# FEV-60_Motor_Driver_Mcu.net
KiCad netlist of a schematic drawn in Altium Designer
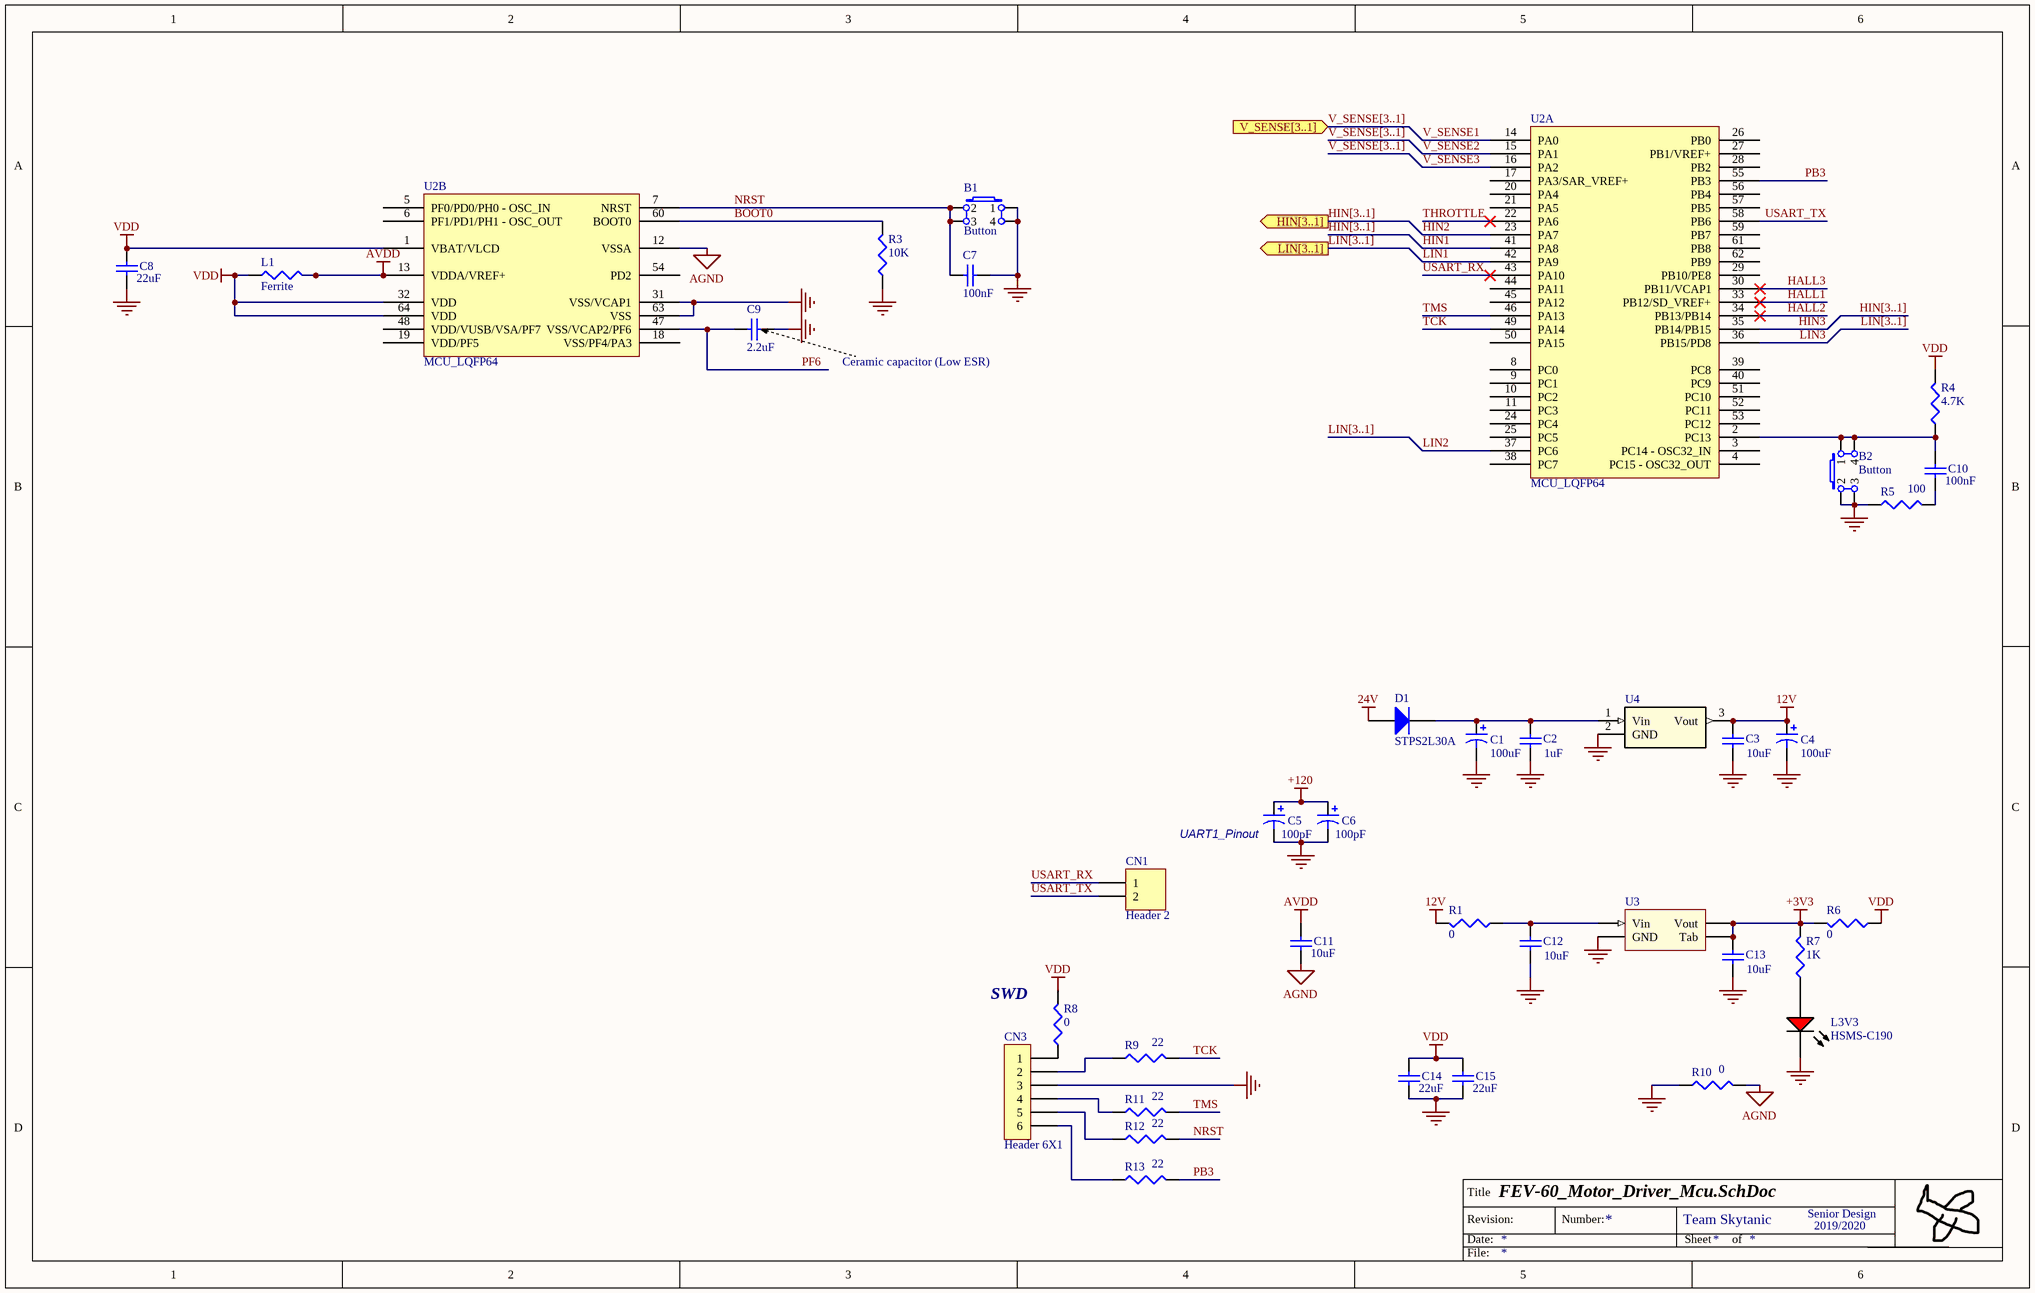
[diagram p0: FEV-60_Motor_Driver_Mcu.SchDoc]

(export (version "E")
  (design (tool "Eeschema 10.0.6"))
  (components
    (comp (ref "B1")
      (value "Button")
      (footprint "Button - duplicate")
      (libsource (lib "FEV-60_Lib") (part "Button"))
    )
    (comp (ref "B2")
      (value "Button")
      (footprint "Button - duplicate")
      (libsource (lib "FEV-60_Lib") (part "Button"))
    )
    (comp (ref "C1")
      (value "100uF")
      (footprint "UVY1V101MED1TD")
      (description "Polarized Capacitor (Axial)")
      (fields (field (name "Comment") "UVY1V101MED1TD") (field (name "PUBLISHER") "Altium Limited"))
      (libsource (lib "FEV-60_Lib") (part "UVY1V101MED1TD"))
    )
    (comp (ref "C2")
      (value "1uF")
      (footprint "1608[0603]")
      (description "Capacitor (Semiconductor SIM Model)")
      (fields (field (name "Comment") "Cap Semi") (field (name "PUBLISHER") "Altium Limited"))
      (libsource (lib "Miscellaneous Devices") (part "Cap Semi"))
    )
    (comp (ref "C3")
      (value "10uF")
      (footprint "1608[0603]")
      (description "Capacitor (Semiconductor SIM Model)")
      (fields (field (name "Comment") "Cap Semi") (field (name "PUBLISHER") "Altium Limited"))
      (libsource (lib "Miscellaneous Devices") (part "Cap Semi"))
    )
    (comp (ref "C4")
      (value "100uF")
      (footprint "UVY1V101MED1TD")
      (description "Polarized Capacitor (Axial)")
      (fields (field (name "Comment") "UVY1V101MED1TD") (field (name "PUBLISHER") "Altium Limited"))
      (libsource (lib "FEV-60_Lib") (part "UVY1V101MED1TD"))
    )
    (comp (ref "C5")
      (value "100pF")
      (footprint "UCS2D151MHD1TN")
      (description "Polarized Capacitor (Axial)")
      (fields (field (name "Comment") "UCS2D151MHD1TN") (field (name "PUBLISHER") "Altium Limited"))
      (libsource (lib "FEV-60_Lib") (part "UCS2D151MHD1TN"))
    )
    (comp (ref "C6")
      (value "100pF")
      (footprint "UCS2D151MHD1TN")
      (description "Polarized Capacitor (Axial)")
      (fields (field (name "Comment") "UCS2D151MHD1TN") (field (name "PUBLISHER") "Altium Limited"))
      (libsource (lib "FEV-60_Lib") (part "UCS2D151MHD1TN"))
    )
    (comp (ref "C7")
      (value "100nF")
      (footprint "1608[0603]")
      (description "Capacitor (Semiconductor SIM Model)")
      (fields (field (name "Comment") "Cap Semi") (field (name "PUBLISHER") "Altium Limited"))
      (libsource (lib "Miscellaneous Devices") (part "Cap Semi"))
    )
    (comp (ref "C8")
      (value "22uF")
      (footprint "1608[0603]")
      (description "Capacitor (Semiconductor SIM Model)")
      (fields (field (name "Comment") "Cap Semi") (field (name "PUBLISHER") "Altium Limited"))
      (libsource (lib "Miscellaneous Devices") (part "Cap Semi"))
    )
    (comp (ref "C9")
      (value "2.2uF")
      (footprint "1608[0603]")
      (description "Capacitor (Semiconductor SIM Model)")
      (fields (field (name "Comment") "Cap Semi") (field (name "PUBLISHER") "Altium Limited"))
      (libsource (lib "Miscellaneous Devices") (part "Cap Semi"))
    )
    (comp (ref "C10")
      (value "100nF")
      (footprint "1608[0603]")
      (description "Capacitor (Semiconductor SIM Model)")
      (fields (field (name "Comment") "Cap Semi") (field (name "PUBLISHER") "Altium Limited"))
      (libsource (lib "Miscellaneous Devices") (part "Cap Semi"))
    )
    (comp (ref "C11")
      (value "10uF")
      (footprint "1608[0603]")
      (description "Capacitor (Semiconductor SIM Model)")
      (fields (field (name "Comment") "Cap Semi") (field (name "PUBLISHER") "Altium Limited"))
      (libsource (lib "Miscellaneous Devices") (part "Cap Semi"))
    )
    (comp (ref "C12")
      (value "10uF")
      (footprint "1608[0603]")
      (description "Capacitor (Semiconductor SIM Model)")
      (fields (field (name "Comment") "Cap Semi") (field (name "PUBLISHER") "Altium Limited"))
      (libsource (lib "Miscellaneous Devices") (part "Cap Semi"))
    )
    (comp (ref "C13")
      (value "10uF")
      (footprint "1608[0603]")
      (description "Capacitor (Semiconductor SIM Model)")
      (fields (field (name "Comment") "Cap Semi") (field (name "PUBLISHER") "Altium Limited"))
      (libsource (lib "Miscellaneous Devices") (part "Cap Semi"))
    )
    (comp (ref "C14")
      (value "22uF")
      (footprint "1608[0603]")
      (description "Capacitor (Semiconductor SIM Model)")
      (fields (field (name "Comment") "Cap Semi") (field (name "PUBLISHER") "Altium Limited"))
      (libsource (lib "Miscellaneous Devices") (part "Cap Semi"))
    )
    (comp (ref "C15")
      (value "22uF")
      (footprint "1608[0603]")
      (description "Capacitor (Semiconductor SIM Model)")
      (fields (field (name "Comment") "Cap Semi") (field (name "PUBLISHER") "Altium Limited"))
      (libsource (lib "Miscellaneous Devices") (part "Cap Semi"))
    )
    (comp (ref "CN1")
      (value "Header 2")
      (footprint "HDR1X2")
      (description "Header, 2-Pin")
      (fields (field (name "PUBLISHER") "Altium Limited"))
      (libsource (lib "Miscellaneous Connectors") (part "Header 2"))
    )
    (comp (ref "CN3")
      (value "Header 6X1")
      (footprint "HDR1X6")
      (description "Header, 6-Pin, Single row")
      (fields (field (name "PUBLISHER") "Altium Limited"))
      (libsource (lib "Nucleo_64") (part "Header 6X1"))
    )
    (comp (ref "D1")
      (value "STPS2L30A")
      (footprint "STPS2L30A")
      (libsource (lib "FEV-60_Lib") (part "STPS2L30A"))
    )
    (comp (ref "L1")
      (value "Ferrite")
      (footprint "J1-0603")
      (description "Resistor")
      (fields (field (name "PUBLISHER") "Altium Limited"))
      (libsource (lib "Miscellaneous Devices") (part "Res3"))
    )
    (comp (ref "L3V3")
      (value "HSMS-C190")
      (footprint "AVAG-HSMX-C190_V")
      (description "LED Uni-Color Red, 52 mW, 20 mA, -40 to 85 degC, 2-Pin SMD, RoHS, Tape and Reel")
      (fields (field (name "MANUFACTURER") "Avago"))
      (libsource (lib "Altium Content Vault") (part "LED-RED-AK-2"))
    )
    (comp (ref "R1")
      (value "0")
      (footprint "J1-0603")
      (description "Resistor")
      (fields (field (name "Comment") "Res3") (field (name "PUBLISHER") "Altium Limited"))
      (libsource (lib "Miscellaneous Devices") (part "Res3"))
    )
    (comp (ref "R3")
      (value "10K")
      (footprint "J1-0603")
      (description "Resistor")
      (fields (field (name "Comment") "Res3") (field (name "PUBLISHER") "Altium Limited"))
      (libsource (lib "Miscellaneous Devices") (part "Res3"))
    )
    (comp (ref "R4")
      (value "4.7K")
      (footprint "J1-0603")
      (description "Resistor")
      (fields (field (name "Comment") "Res3") (field (name "PUBLISHER") "Altium Limited"))
      (libsource (lib "Miscellaneous Devices") (part "Res3"))
    )
    (comp (ref "R5")
      (value "100")
      (footprint "J1-0603")
      (description "Resistor")
      (fields (field (name "Comment") "Res3") (field (name "PUBLISHER") "Altium Limited"))
      (libsource (lib "Miscellaneous Devices") (part "Res3"))
    )
    (comp (ref "R6")
      (value "0")
      (footprint "J1-0603")
      (description "Resistor")
      (fields (field (name "Comment") "Res3") (field (name "PUBLISHER") "Altium Limited"))
      (libsource (lib "Miscellaneous Devices") (part "Res3"))
    )
    (comp (ref "R7")
      (value "1K")
      (footprint "J1-0603")
      (description "Resistor")
      (fields (field (name "Comment") "Res3") (field (name "PUBLISHER") "Altium Limited"))
      (libsource (lib "Miscellaneous Devices") (part "Res3"))
    )
    (comp (ref "R8")
      (value "0")
      (footprint "J1-0603")
      (description "Resistor")
      (fields (field (name "Comment") "Res3") (field (name "PUBLISHER") "Altium Limited"))
      (libsource (lib "Miscellaneous Devices") (part "Res3"))
    )
    (comp (ref "R9")
      (value "22")
      (footprint "J1-0603")
      (description "Resistor")
      (fields (field (name "Comment") "Res3") (field (name "PUBLISHER") "Altium Limited"))
      (libsource (lib "Miscellaneous Devices") (part "Res3"))
    )
    (comp (ref "R10")
      (value "0")
      (footprint "J1-0603")
      (description "Resistor")
      (fields (field (name "Comment") "Res3") (field (name "PUBLISHER") "Altium Limited"))
      (libsource (lib "Miscellaneous Devices") (part "Res3"))
    )
    (comp (ref "R11")
      (value "22")
      (footprint "J1-0603")
      (description "Resistor")
      (fields (field (name "Comment") "Res3") (field (name "PUBLISHER") "Altium Limited"))
      (libsource (lib "Miscellaneous Devices") (part "Res3"))
    )
    (comp (ref "R12")
      (value "22")
      (footprint "J1-0603")
      (description "Resistor")
      (fields (field (name "Comment") "Res3") (field (name "PUBLISHER") "Altium Limited"))
      (libsource (lib "Miscellaneous Devices") (part "Res3"))
    )
    (comp (ref "R13")
      (value "22")
      (footprint "J1-0603")
      (description "Resistor")
      (fields (field (name "Comment") "Res3") (field (name "PUBLISHER") "Altium Limited"))
      (libsource (lib "Miscellaneous Devices") (part "Res3"))
    )
    (comp (ref "U2")
      (value "MCU_LQFP64")
      (footprint "STM32F030R8 - duplicate")
      (libsource (lib "FEV-60_Lib") (part "MCU_LQFP64"))
    )
    (comp (ref "U3")
      (value "LD1117S33TR")
      (footprint "LD1117S33TR - duplicate")
      (libsource (lib "FEV-60_Lib") (part "LD1117S33TR"))
    )
    (comp (ref "U4")
      (value "UA78M12CKVURG3")
      (footprint "UA78M12CKVURG3")
      (description "No Description Available")
      (fields
        (field (name "MANUFACTURER") "Texas Instruments")
        (field (name "COPYRIGHT") "Copyright (C) 2018 Accelerated Designs. All rights reserved")
      )
      (libsource (lib "FEV-60_Lib") (part "UA78M12CKVURG3"))
    )
  )
  (nets
    (net (code "1") (name "+3V3") (class "Default")
      (node (ref "C13") (pin "2") (pinfunction "2_2") (pintype "passive"))
      (node (ref "R6") (pin "2") (pinfunction "2_2") (pintype "passive"))
      (node (ref "R7") (pin "2") (pinfunction "2_2") (pintype "passive"))
      (node (ref "U3") (pin "2") (pinfunction "Vout_2") (pintype "passive"))
      (node (ref "U3") (pin "4") (pinfunction "Tab_4") (pintype "passive"))
    )
    (net (code "2") (name "+120") (class "Default")
      (node (ref "C5") (pin "1") (pinfunction "1_1") (pintype "passive"))
      (node (ref "C6") (pin "1") (pinfunction "1_1") (pintype "passive"))
    )
    (net (code "3") (name "/BOOT0") (class "Default")
      (node (ref "R3") (pin "2") (pinfunction "2_2") (pintype "passive"))
      (node (ref "U2") (pin "60") (pinfunction "BOOT0_60") (pintype "passive"))
    )
    (net (code "4") (name "/HALL1") (class "Default")
      (node (ref "U2") (pin "33") (pinfunction "PB12/SD_VREF+_33") (pintype "passive+no_connect"))
    )
    (net (code "5") (name "/HALL2") (class "Default")
      (node (ref "U2") (pin "34") (pinfunction "PB13/PB14_34") (pintype "passive+no_connect"))
    )
    (net (code "6") (name "/HALL3") (class "Default")
      (node (ref "U2") (pin "30") (pinfunction "PB11/VCAP1_30") (pintype "passive+no_connect"))
    )
    (net (code "7") (name "/HIN1") (class "Default")
      (node (ref "U2") (pin "41") (pinfunction "PA8_41") (pintype "passive"))
    )
    (net (code "8") (name "/HIN2") (class "Default")
      (node (ref "U2") (pin "23") (pinfunction "PA7_23") (pintype "passive"))
    )
    (net (code "9") (name "/HIN3") (class "Default")
      (node (ref "U2") (pin "35") (pinfunction "PB14/PB15_35") (pintype "passive"))
    )
    (net (code "11") (name "/LIN1") (class "Default")
      (node (ref "U2") (pin "42") (pinfunction "PA9_42") (pintype "passive"))
    )
    (net (code "12") (name "/LIN2") (class "Default")
      (node (ref "U2") (pin "37") (pinfunction "PC6_37") (pintype "passive"))
    )
    (net (code "13") (name "/LIN3") (class "Default")
      (node (ref "U2") (pin "36") (pinfunction "PB15/PD8_36") (pintype "passive"))
    )
    (net (code "15") (name "/NRST") (class "Default")
      (node (ref "B1") (pin "2") (pinfunction "2_2") (pintype "passive"))
      (node (ref "B1") (pin "3") (pinfunction "3_3") (pintype "passive"))
      (node (ref "C7") (pin "2") (pinfunction "2_2") (pintype "passive"))
      (node (ref "R12") (pin "2") (pinfunction "2_2") (pintype "passive"))
      (node (ref "U2") (pin "7") (pinfunction "NRST_7") (pintype "passive"))
    )
    (net (code "16") (name "/PB3") (class "Default")
      (node (ref "R13") (pin "2") (pinfunction "2_2") (pintype "passive"))
      (node (ref "U2") (pin "55") (pinfunction "PB3_55") (pintype "passive"))
    )
    (net (code "17") (name "/PF6") (class "Default")
      (node (ref "C9") (pin "2") (pinfunction "2_2") (pintype "passive"))
      (node (ref "U2") (pin "47") (pinfunction "VSS/VCAP2/PF6_47") (pintype "passive"))
    )
    (net (code "18") (name "/TCK") (class "Default")
      (node (ref "R9") (pin "2") (pinfunction "2_2") (pintype "passive"))
      (node (ref "U2") (pin "49") (pinfunction "PA14_49") (pintype "passive"))
    )
    (net (code "19") (name "/THROTTLE") (class "Default")
      (node (ref "U2") (pin "22") (pinfunction "PA6_22") (pintype "passive+no_connect"))
    )
    (net (code "20") (name "/TMS") (class "Default")
      (node (ref "R11") (pin "2") (pinfunction "2_2") (pintype "passive"))
      (node (ref "U2") (pin "46") (pinfunction "PA13_46") (pintype "passive"))
    )
    (net (code "21") (name "/USART_RX") (class "Default")
      (node (ref "CN1") (pin "1") (pinfunction "1_1") (pintype "passive"))
      (node (ref "U2") (pin "43") (pinfunction "PA10_43") (pintype "passive"))
    )
    (net (code "22") (name "/USART_TX") (class "Default")
      (node (ref "CN1") (pin "2") (pinfunction "2_2") (pintype "passive"))
      (node (ref "U2") (pin "58") (pinfunction "PB6_58") (pintype "passive"))
    )
    (net (code "23") (name "/V_SENSE1") (class "Default")
      (node (ref "U2") (pin "14") (pinfunction "PA0_14") (pintype "passive"))
    )
    (net (code "24") (name "/V_SENSE2") (class "Default")
      (node (ref "U2") (pin "15") (pinfunction "PA1_15") (pintype "passive"))
    )
    (net (code "25") (name "/V_SENSE3") (class "Default")
      (node (ref "U2") (pin "16") (pinfunction "PA2_16") (pintype "passive"))
    )
    (net (code "27") (name "12V") (class "Default")
      (node (ref "C3") (pin "2") (pinfunction "2_2") (pintype "passive"))
      (node (ref "C4") (pin "1") (pinfunction "1_1") (pintype "passive"))
      (node (ref "R1") (pin "2") (pinfunction "2_2") (pintype "passive"))
      (node (ref "U4") (pin "3") (pinfunction "Vout_3") (pintype "output"))
    )
    (net (code "28") (name "24V") (class "Default")
      (node (ref "D1") (pin "1") (pinfunction "A_1") (pintype "passive"))
    )
    (net (code "29") (name "AGND") (class "Default")
      (node (ref "C11") (pin "1") (pinfunction "1_1") (pintype "passive"))
      (node (ref "R10") (pin "2") (pinfunction "2_2") (pintype "passive"))
      (node (ref "U2") (pin "12") (pinfunction "VSSA_12") (pintype "passive"))
    )
    (net (code "30") (name "AVDD") (class "Default")
      (node (ref "C11") (pin "2") (pinfunction "2_2") (pintype "passive"))
      (node (ref "L1") (pin "2") (pinfunction "2_2") (pintype "passive"))
      (node (ref "U2") (pin "13") (pinfunction "VDDA/VREF+_13") (pintype "passive"))
    )
    (net (code "31") (name "GND") (class "Default")
      (node (ref "B1") (pin "1") (pinfunction "1_1") (pintype "passive"))
      (node (ref "B1") (pin "4") (pinfunction "4_4") (pintype "passive"))
      (node (ref "B2") (pin "2") (pinfunction "2_2") (pintype "passive"))
      (node (ref "B2") (pin "3") (pinfunction "3_3") (pintype "passive"))
      (node (ref "C1") (pin "2") (pinfunction "2_2") (pintype "passive"))
      (node (ref "C12") (pin "1") (pinfunction "1_1") (pintype "passive"))
      (node (ref "C13") (pin "1") (pinfunction "1_1") (pintype "passive"))
      (node (ref "C14") (pin "1") (pinfunction "1_1") (pintype "passive"))
      (node (ref "C15") (pin "1") (pinfunction "1_1") (pintype "passive"))
      (node (ref "C2") (pin "1") (pinfunction "1_1") (pintype "passive"))
      (node (ref "C3") (pin "1") (pinfunction "1_1") (pintype "passive"))
      (node (ref "C4") (pin "2") (pinfunction "2_2") (pintype "passive"))
      (node (ref "C5") (pin "2") (pinfunction "2_2") (pintype "passive"))
      (node (ref "C6") (pin "2") (pinfunction "2_2") (pintype "passive"))
      (node (ref "C7") (pin "1") (pinfunction "1_1") (pintype "passive"))
      (node (ref "C8") (pin "1") (pinfunction "1_1") (pintype "passive"))
      (node (ref "C9") (pin "1") (pinfunction "1_1") (pintype "passive"))
      (node (ref "CN3") (pin "3") (pinfunction "3_3") (pintype "passive"))
      (node (ref "L3V3") (pin "2") (pinfunction "K_2") (pintype "passive"))
      (node (ref "R10") (pin "1") (pinfunction "1_1") (pintype "passive"))
      (node (ref "R3") (pin "1") (pinfunction "1_1") (pintype "passive"))
      (node (ref "R5") (pin "1") (pinfunction "1_1") (pintype "passive"))
      (node (ref "U2") (pin "31") (pinfunction "VSS/VCAP1_31") (pintype "passive"))
      (node (ref "U2") (pin "63") (pinfunction "VSS_63") (pintype "passive"))
      (node (ref "U3") (pin "1") (pinfunction "GND_1") (pintype "passive"))
      (node (ref "U4") (pin "2") (pinfunction "GND_2") (pintype "power_in"))
    )
    (net (code "32") (name "Net-(C10-Pad1)") (class "Default")
      (node (ref "C10") (pin "1") (pinfunction "1_1") (pintype "passive"))
      (node (ref "R5") (pin "2") (pinfunction "2_2") (pintype "passive"))
    )
    (net (code "33") (name "Net-(CN3-Pad1)") (class "Default")
      (node (ref "CN3") (pin "1") (pinfunction "1_1") (pintype "passive"))
      (node (ref "R8") (pin "1") (pinfunction "1_1") (pintype "passive"))
    )
    (net (code "34") (name "Net-(CN3-Pad2)") (class "Default")
      (node (ref "CN3") (pin "2") (pinfunction "2_2") (pintype "passive"))
      (node (ref "R9") (pin "1") (pinfunction "1_1") (pintype "passive"))
    )
    (net (code "35") (name "Net-(CN3-Pad4)") (class "Default")
      (node (ref "CN3") (pin "4") (pinfunction "4_4") (pintype "passive"))
      (node (ref "R11") (pin "1") (pinfunction "1_1") (pintype "passive"))
    )
    (net (code "36") (name "Net-(CN3-Pad5)") (class "Default")
      (node (ref "CN3") (pin "5") (pinfunction "5_5") (pintype "passive"))
      (node (ref "R12") (pin "1") (pinfunction "1_1") (pintype "passive"))
    )
    (net (code "37") (name "Net-(CN3-Pad6)") (class "Default")
      (node (ref "CN3") (pin "6") (pinfunction "6_6") (pintype "passive"))
      (node (ref "R13") (pin "1") (pinfunction "1_1") (pintype "passive"))
    )
    (net (code "38") (name "Net-(D1-K)") (class "Default")
      (node (ref "C1") (pin "1") (pinfunction "1_1") (pintype "passive"))
      (node (ref "C2") (pin "2") (pinfunction "2_2") (pintype "passive"))
      (node (ref "D1") (pin "2") (pinfunction "K_2") (pintype "passive"))
      (node (ref "U4") (pin "1") (pinfunction "Vin_1") (pintype "input"))
    )
    (net (code "39") (name "Net-(L3V3-A)") (class "Default")
      (node (ref "L3V3") (pin "1") (pinfunction "A_1") (pintype "passive"))
      (node (ref "R7") (pin "1") (pinfunction "1_1") (pintype "passive"))
    )
    (net (code "40") (name "Net-(U2A-PC13)") (class "Default")
      (node (ref "B2") (pin "1") (pinfunction "1_1") (pintype "passive"))
      (node (ref "B2") (pin "4") (pinfunction "4_4") (pintype "passive"))
      (node (ref "C10") (pin "2") (pinfunction "2_2") (pintype "passive"))
      (node (ref "R4") (pin "1") (pinfunction "1_1") (pintype "passive"))
      (node (ref "U2") (pin "2") (pinfunction "PC13_2") (pintype "passive"))
    )
    (net (code "41") (name "Net-(U3-Vin)") (class "Default")
      (node (ref "C12") (pin "2") (pinfunction "2_2") (pintype "passive"))
      (node (ref "R1") (pin "1") (pinfunction "1_1") (pintype "passive"))
      (node (ref "U3") (pin "3") (pinfunction "Vin_3") (pintype "input"))
    )
    (net (code "42") (name "VDD") (class "Default")
      (node (ref "C14") (pin "2") (pinfunction "2_2") (pintype "passive"))
      (node (ref "C15") (pin "2") (pinfunction "2_2") (pintype "passive"))
      (node (ref "C8") (pin "2") (pinfunction "2_2") (pintype "passive"))
      (node (ref "L1") (pin "1") (pinfunction "1_1") (pintype "passive"))
      (node (ref "R4") (pin "2") (pinfunction "2_2") (pintype "passive"))
      (node (ref "R6") (pin "1") (pinfunction "1_1") (pintype "passive"))
      (node (ref "R8") (pin "2") (pinfunction "2_2") (pintype "passive"))
      (node (ref "U2") (pin "1") (pinfunction "VBAT/VLCD_1") (pintype "passive"))
      (node (ref "U2") (pin "32") (pinfunction "VDD_32") (pintype "passive"))
      (node (ref "U2") (pin "64") (pinfunction "VDD_64") (pintype "passive"))
    )
    (net (code "43") (name "unconnected-(U2A-PA3{slash}SAR_VREF+-Pad17)") (class "Default")
      (node (ref "U2") (pin "17") (pinfunction "PA3/SAR_VREF+_17") (pintype "passive"))
    )
    (net (code "44") (name "unconnected-(U2A-PA4-Pad20)") (class "Default")
      (node (ref "U2") (pin "20") (pinfunction "PA4_20") (pintype "passive"))
    )
    (net (code "45") (name "unconnected-(U2A-PA5-Pad21)") (class "Default")
      (node (ref "U2") (pin "21") (pinfunction "PA5_21") (pintype "passive"))
    )
    (net (code "46") (name "unconnected-(U2A-PA11-Pad44)") (class "Default")
      (node (ref "U2") (pin "44") (pinfunction "PA11_44") (pintype "passive"))
    )
    (net (code "47") (name "unconnected-(U2A-PA12-Pad45)") (class "Default")
      (node (ref "U2") (pin "45") (pinfunction "PA12_45") (pintype "passive"))
    )
    (net (code "48") (name "unconnected-(U2A-PA15-Pad50)") (class "Default")
      (node (ref "U2") (pin "50") (pinfunction "PA15_50") (pintype "passive"))
    )
    (net (code "49") (name "unconnected-(U2A-PB0-Pad26)") (class "Default")
      (node (ref "U2") (pin "26") (pinfunction "PB0_26") (pintype "passive"))
    )
    (net (code "50") (name "unconnected-(U2A-PB1{slash}VREF+-Pad27)") (class "Default")
      (node (ref "U2") (pin "27") (pinfunction "PB1/VREF+_27") (pintype "passive"))
    )
    (net (code "51") (name "unconnected-(U2A-PB2-Pad28)") (class "Default")
      (node (ref "U2") (pin "28") (pinfunction "PB2_28") (pintype "passive"))
    )
    (net (code "52") (name "unconnected-(U2A-PB4-Pad56)") (class "Default")
      (node (ref "U2") (pin "56") (pinfunction "PB4_56") (pintype "passive"))
    )
    (net (code "53") (name "unconnected-(U2A-PB5-Pad57)") (class "Default")
      (node (ref "U2") (pin "57") (pinfunction "PB5_57") (pintype "passive"))
    )
    (net (code "54") (name "unconnected-(U2A-PB7-Pad59)") (class "Default")
      (node (ref "U2") (pin "59") (pinfunction "PB7_59") (pintype "passive"))
    )
    (net (code "55") (name "unconnected-(U2A-PB8-Pad61)") (class "Default")
      (node (ref "U2") (pin "61") (pinfunction "PB8_61") (pintype "passive"))
    )
    (net (code "56") (name "unconnected-(U2A-PB9-Pad62)") (class "Default")
      (node (ref "U2") (pin "62") (pinfunction "PB9_62") (pintype "passive"))
    )
    (net (code "57") (name "unconnected-(U2A-PB10{slash}PE8-Pad29)") (class "Default")
      (node (ref "U2") (pin "29") (pinfunction "PB10/PE8_29") (pintype "passive"))
    )
    (net (code "58") (name "unconnected-(U2A-PC0-Pad8)") (class "Default")
      (node (ref "U2") (pin "8") (pinfunction "PC0_8") (pintype "passive"))
    )
    (net (code "59") (name "unconnected-(U2A-PC1-Pad9)") (class "Default")
      (node (ref "U2") (pin "9") (pinfunction "PC1_9") (pintype "passive"))
    )
    (net (code "60") (name "unconnected-(U2A-PC2-Pad10)") (class "Default")
      (node (ref "U2") (pin "10") (pinfunction "PC2_10") (pintype "passive"))
    )
    (net (code "61") (name "unconnected-(U2A-PC3-Pad11)") (class "Default")
      (node (ref "U2") (pin "11") (pinfunction "PC3_11") (pintype "passive"))
    )
    (net (code "62") (name "unconnected-(U2A-PC4-Pad24)") (class "Default")
      (node (ref "U2") (pin "24") (pinfunction "PC4_24") (pintype "passive"))
    )
    (net (code "63") (name "unconnected-(U2A-PC5-Pad25)") (class "Default")
      (node (ref "U2") (pin "25") (pinfunction "PC5_25") (pintype "passive"))
    )
    (net (code "64") (name "unconnected-(U2A-PC7-Pad38)") (class "Default")
      (node (ref "U2") (pin "38") (pinfunction "PC7_38") (pintype "passive"))
    )
    (net (code "65") (name "unconnected-(U2A-PC8-Pad39)") (class "Default")
      (node (ref "U2") (pin "39") (pinfunction "PC8_39") (pintype "passive"))
    )
    (net (code "66") (name "unconnected-(U2A-PC9-Pad40)") (class "Default")
      (node (ref "U2") (pin "40") (pinfunction "PC9_40") (pintype "passive"))
    )
    (net (code "67") (name "unconnected-(U2A-PC10-Pad51)") (class "Default")
      (node (ref "U2") (pin "51") (pinfunction "PC10_51") (pintype "passive"))
    )
    (net (code "68") (name "unconnected-(U2A-PC11-Pad52)") (class "Default")
      (node (ref "U2") (pin "52") (pinfunction "PC11_52") (pintype "passive"))
    )
    (net (code "69") (name "unconnected-(U2A-PC12-Pad53)") (class "Default")
      (node (ref "U2") (pin "53") (pinfunction "PC12_53") (pintype "passive"))
    )
    (net (code "70") (name "unconnected-(U2A-PC14_-_OSC32_IN-Pad3)") (class "Default")
      (node (ref "U2") (pin "3") (pinfunction "PC14_-_OSC32_IN_3") (pintype "passive"))
    )
    (net (code "71") (name "unconnected-(U2A-PC15_-_OSC32_OUT-Pad4)") (class "Default")
      (node (ref "U2") (pin "4") (pinfunction "PC15_-_OSC32_OUT_4") (pintype "passive"))
    )
    (net (code "72") (name "unconnected-(U2B-PD2-Pad54)") (class "Default")
      (node (ref "U2") (pin "54") (pinfunction "PD2_54") (pintype "passive"))
    )
    (net (code "73") (name "unconnected-(U2B-PF0{slash}PD0{slash}PH0_-_OSC_IN-Pad5)") (class "Default")
      (node (ref "U2") (pin "5") (pinfunction "PF0/PD0/PH0_-_OSC_IN_5") (pintype "passive"))
    )
    (net (code "74") (name "unconnected-(U2B-PF1{slash}PD1{slash}PH1_-_OSC_OUT-Pad6)") (class "Default")
      (node (ref "U2") (pin "6") (pinfunction "PF1/PD1/PH1_-_OSC_OUT_6") (pintype "passive"))
    )
    (net (code "75") (name "unconnected-(U2B-VDD{slash}PF5-Pad19)") (class "Default")
      (node (ref "U2") (pin "19") (pinfunction "VDD/PF5_19") (pintype "passive"))
    )
    (net (code "76") (name "unconnected-(U2B-VDD{slash}VUSB{slash}VSA{slash}PF7-Pad48)") (class "Default")
      (node (ref "U2") (pin "48") (pinfunction "VDD/VUSB/VSA/PF7_48") (pintype "passive"))
    )
    (net (code "77") (name "unconnected-(U2B-VSS{slash}PF4{slash}PA3-Pad18)") (class "Default")
      (node (ref "U2") (pin "18") (pinfunction "VSS/PF4/PA3_18") (pintype "passive"))
    )
  )
)
